# SWD-Adapter.net
KiCad netlist of a schematic drawn in EAGLE
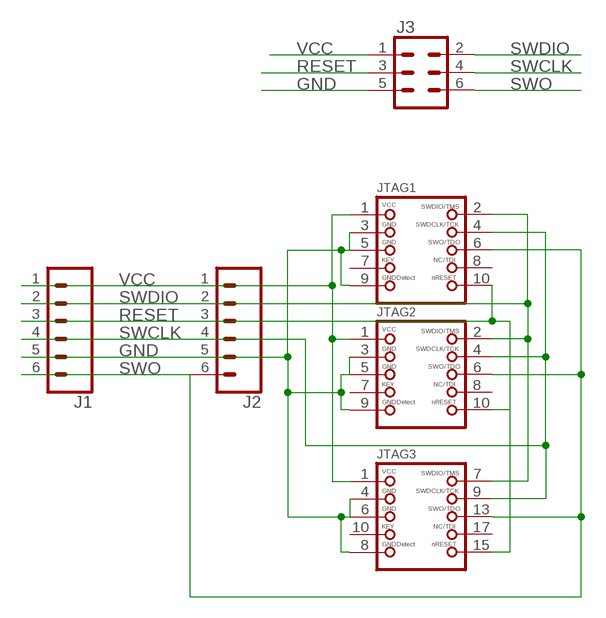
[diagram p0: schematic, sheet 1]

(export (version "E")
  (design (tool "Eeschema 10.0.6"))
  (components
    (comp (ref "J1")
      (value "CONN_06SILK_FEMALE_PTH")
      (footprint "eagle-import:1X06")
      (libsource (lib "eagle-import") (part "CONN_06SILK_FEMALE_PTH"))
    )
    (comp (ref "J2")
      (value "CONN_06SILK_FEMALE_PTH")
      (footprint "eagle-import:1X06")
      (libsource (lib "eagle-import") (part "CONN_06SILK_FEMALE_PTH"))
    )
    (comp (ref "J3")
      (value "CONN_03X2NO_SILK")
      (footprint "eagle-import:2X3-NS")
      (libsource (lib "eagle-import") (part "CONN_03X2NO_SILK"))
    )
    (comp (ref "JTAG1")
      (value "JTAG-CORTEXM3")
      (footprint "eagle-import:2X05_1.27MM_SMT")
      (libsource (lib "eagle-import") (part "JTAG-CORTEXM3"))
    )
    (comp (ref "JTAG2")
      (value "JTAG-CORTEXM3MOLEX")
      (footprint "eagle-import:CORTEXM3_SWD10_MOLEX")
      (libsource (lib "eagle-import") (part "JTAG-CORTEXM3MOLEX"))
    )
    (comp (ref "JTAG3")
      (value "JTAG-CORTEXM3MOLEX20")
      (footprint "eagle-import:JTAG-ARM")
      (libsource (lib "eagle-import") (part "JTAG-CORTEXM3MOLEX20"))
    )
  )
  (nets
    (net (code "1") (name "/GND") (class "Default")
      (node (ref "J1") (pin "5") (pinfunction "5_5") (pintype "passive"))
      (node (ref "J2") (pin "5") (pinfunction "5_5") (pintype "passive"))
      (node (ref "J3") (pin "5") (pinfunction "5_5") (pintype "bidirectional"))
      (node (ref "JTAG1") (pin "3") (pinfunction "3_3") (pintype "passive"))
      (node (ref "JTAG1") (pin "5") (pinfunction "5_5") (pintype "passive"))
      (node (ref "JTAG1") (pin "9") (pinfunction "9_9") (pintype "passive"))
      (node (ref "JTAG2") (pin "3") (pinfunction "3_3") (pintype "passive"))
      (node (ref "JTAG2") (pin "5") (pinfunction "5_5") (pintype "passive"))
      (node (ref "JTAG2") (pin "9") (pinfunction "9_9") (pintype "passive"))
      (node (ref "JTAG3") (pin "4") (pinfunction "3_4") (pintype "passive"))
      (node (ref "JTAG3") (pin "6") (pinfunction "5_6") (pintype "passive"))
      (node (ref "JTAG3") (pin "8") (pinfunction "9_8") (pintype "passive"))
    )
    (net (code "2") (name "/RESET") (class "Default")
      (node (ref "J1") (pin "3") (pinfunction "3_3") (pintype "passive"))
      (node (ref "J2") (pin "3") (pinfunction "3_3") (pintype "passive"))
      (node (ref "J3") (pin "3") (pinfunction "3_3") (pintype "bidirectional"))
      (node (ref "JTAG1") (pin "10") (pinfunction "10_10") (pintype "passive"))
      (node (ref "JTAG2") (pin "10") (pinfunction "10_10") (pintype "passive"))
      (node (ref "JTAG3") (pin "15") (pinfunction "10_15") (pintype "passive"))
    )
    (net (code "3") (name "/SWCLK") (class "Default")
      (node (ref "J1") (pin "4") (pinfunction "4_4") (pintype "passive"))
      (node (ref "J2") (pin "4") (pinfunction "4_4") (pintype "passive"))
      (node (ref "J3") (pin "4") (pinfunction "4_4") (pintype "bidirectional"))
      (node (ref "JTAG1") (pin "4") (pinfunction "4_4") (pintype "passive"))
      (node (ref "JTAG2") (pin "4") (pinfunction "4_4") (pintype "passive"))
      (node (ref "JTAG3") (pin "9") (pinfunction "4_9") (pintype "passive"))
    )
    (net (code "4") (name "/SWDIO") (class "Default")
      (node (ref "J1") (pin "2") (pinfunction "2_2") (pintype "passive"))
      (node (ref "J2") (pin "2") (pinfunction "2_2") (pintype "passive"))
      (node (ref "J3") (pin "2") (pinfunction "2_2") (pintype "bidirectional"))
      (node (ref "JTAG1") (pin "2") (pinfunction "2_2") (pintype "passive"))
      (node (ref "JTAG2") (pin "2") (pinfunction "2_2") (pintype "passive"))
      (node (ref "JTAG3") (pin "7") (pinfunction "2_7") (pintype "passive"))
    )
    (net (code "5") (name "/SWO") (class "Default")
      (node (ref "J1") (pin "6") (pinfunction "6_6") (pintype "passive"))
      (node (ref "J2") (pin "6") (pinfunction "6_6") (pintype "passive"))
      (node (ref "J3") (pin "6") (pinfunction "6_6") (pintype "bidirectional"))
      (node (ref "JTAG1") (pin "6") (pinfunction "6_6") (pintype "passive"))
      (node (ref "JTAG2") (pin "6") (pinfunction "6_6") (pintype "passive"))
      (node (ref "JTAG3") (pin "13") (pinfunction "6_13") (pintype "passive"))
    )
    (net (code "6") (name "/VCC") (class "Default")
      (node (ref "J1") (pin "1") (pinfunction "1_1") (pintype "passive"))
      (node (ref "J2") (pin "1") (pinfunction "1_1") (pintype "passive"))
      (node (ref "J3") (pin "1") (pinfunction "1_1") (pintype "bidirectional"))
      (node (ref "JTAG1") (pin "1") (pinfunction "1_1") (pintype "passive"))
      (node (ref "JTAG2") (pin "1") (pinfunction "1_1") (pintype "passive"))
      (node (ref "JTAG3") (pin "1") (pinfunction "1_1") (pintype "passive"))
    )
    (net (code "7") (name "unconnected-(JTAG1-Pad7)") (class "Default")
      (node (ref "JTAG1") (pin "7") (pinfunction "7_7") (pintype "passive"))
    )
    (net (code "8") (name "unconnected-(JTAG1-Pad8)") (class "Default")
      (node (ref "JTAG1") (pin "8") (pinfunction "8_8") (pintype "passive"))
    )
    (net (code "9") (name "unconnected-(JTAG2-Pad7)") (class "Default")
      (node (ref "JTAG2") (pin "7") (pinfunction "7_7") (pintype "passive"))
    )
    (net (code "10") (name "unconnected-(JTAG2-Pad8)") (class "Default")
      (node (ref "JTAG2") (pin "8") (pinfunction "8_8") (pintype "passive"))
    )
    (net (code "11") (name "unconnected-(JTAG3-7-Pad10)") (class "Default")
      (node (ref "JTAG3") (pin "10") (pinfunction "7_10") (pintype "passive"))
    )
    (net (code "12") (name "unconnected-(JTAG3-8-Pad17)") (class "Default")
      (node (ref "JTAG3") (pin "17") (pinfunction "8_17") (pintype "passive"))
    )
  )
)
